# PCB-JACKGPI.net
KiCad netlist of a schematic drawn in EAGLE
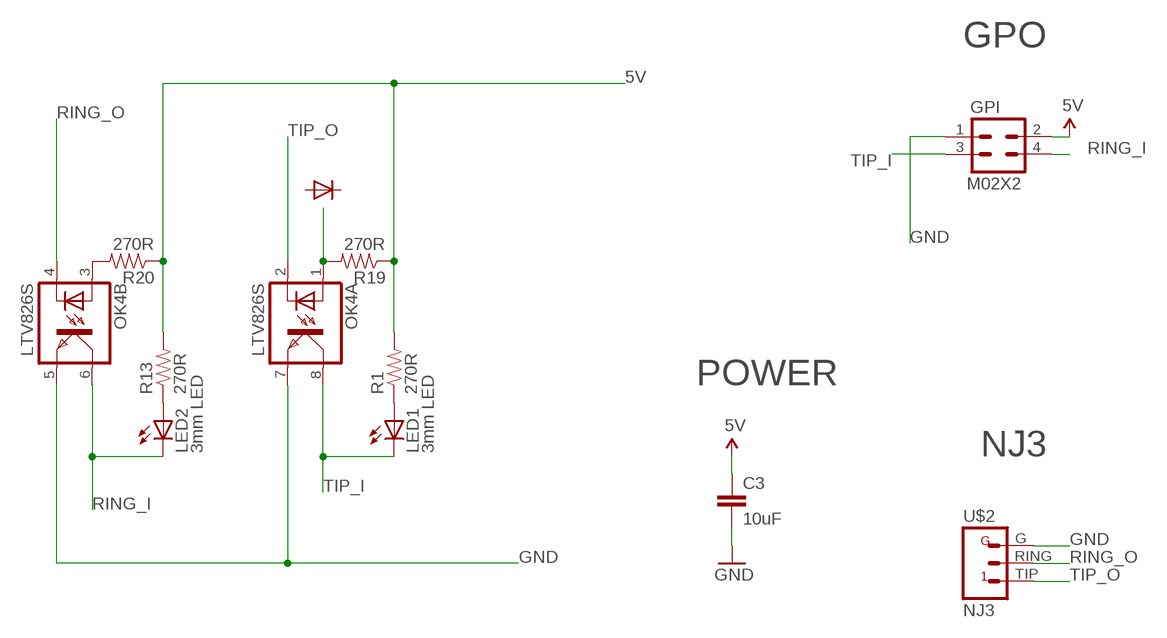
[diagram p0: schematic, sheet 1]

(export (version "E")
  (design (tool "Eeschema 10.0.6"))
  (components
    (comp (ref "C3")
      (value "10uF")
      (footprint "eagle-import:0805")
      (libsource (lib "eagle-import") (part "CAP0805"))
    )
    (comp (ref "GPI")
      (value "M02X2")
      (footprint "eagle-import:2X2")
      (libsource (lib "eagle-import") (part "M02X2"))
    )
    (comp (ref "LED1")
      (value "3mm LED")
      (footprint "eagle-import:LED3MM")
      (libsource (lib "eagle-import") (part "LED3MM"))
    )
    (comp (ref "LED2")
      (value "3mm LED")
      (footprint "eagle-import:LED3MM")
      (libsource (lib "eagle-import") (part "LED3MM"))
    )
    (comp (ref "OK4")
      (value "LTV826S")
      (footprint "eagle-import:DIL8-SMD")
      (libsource (lib "eagle-import") (part "LTV826S"))
    )
    (comp (ref "R1")
      (value "270R")
      (footprint "eagle-import:0603-RES")
      (libsource (lib "eagle-import") (part "RESISTOR0603-RES"))
    )
    (comp (ref "R13")
      (value "270R")
      (footprint "eagle-import:0603-RES")
      (libsource (lib "eagle-import") (part "RESISTOR0603-RES"))
    )
    (comp (ref "R19")
      (value "270R")
      (footprint "eagle-import:0603-RES")
      (libsource (lib "eagle-import") (part "RESISTOR0603-RES"))
    )
    (comp (ref "R20")
      (value "270R")
      (footprint "eagle-import:0603-RES")
      (libsource (lib "eagle-import") (part "RESISTOR0603-RES"))
    )
    (comp (ref "U$2")
      (value "NJ3")
      (footprint "eagle-import:NJ3FP6C")
      (libsource (lib "eagle-import") (part "NJ3"))
    )
  )
  (nets
    (net (code "1") (name "/RING_I") (class "Default")
      (node (ref "GPI") (pin "4") (pinfunction "4_4") (pintype "passive"))
      (node (ref "LED2") (pin "K") (pinfunction "C_K") (pintype "passive"))
      (node (ref "OK4") (pin "6") (pinfunction "COL_6") (pintype "passive"))
    )
    (net (code "2") (name "/RING_O") (class "Default")
      (node (ref "OK4") (pin "4") (pinfunction "C_4") (pintype "passive"))
      (node (ref "U$2") (pin "RING") (pinfunction "2_RING") (pintype "passive"))
    )
    (net (code "3") (name "/TIP_I") (class "Default")
      (node (ref "GPI") (pin "3") (pinfunction "3_3") (pintype "passive"))
      (node (ref "LED1") (pin "K") (pinfunction "C_K") (pintype "passive"))
      (node (ref "OK4") (pin "8") (pinfunction "COL_8") (pintype "passive"))
    )
    (net (code "4") (name "/TIP_O") (class "Default")
      (node (ref "OK4") (pin "2") (pinfunction "C_2") (pintype "passive"))
      (node (ref "U$2") (pin "TIP") (pinfunction "1_TIP") (pintype "passive"))
    )
    (net (code "5") (name "5V") (class "Default")
      (node (ref "C3") (pin "1") (pinfunction "1_1") (pintype "passive"))
      (node (ref "GPI") (pin "2") (pinfunction "2_2") (pintype "passive"))
      (node (ref "R1") (pin "2") (pinfunction "2_2") (pintype "passive"))
      (node (ref "R13") (pin "2") (pinfunction "2_2") (pintype "passive"))
      (node (ref "R19") (pin "1") (pinfunction "1_1") (pintype "passive"))
      (node (ref "R20") (pin "1") (pinfunction "1_1") (pintype "passive"))
    )
    (net (code "6") (name "GND") (class "Default")
      (node (ref "C3") (pin "2") (pinfunction "2_2") (pintype "passive"))
      (node (ref "GPI") (pin "1") (pinfunction "1_1") (pintype "passive"))
      (node (ref "OK4") (pin "5") (pinfunction "EMIT_5") (pintype "passive"))
      (node (ref "OK4") (pin "7") (pinfunction "EMIT_7") (pintype "passive"))
      (node (ref "U$2") (pin "G") (pinfunction "G_G") (pintype "power_in"))
    )
    (net (code "7") (name "Net-(LED1-PadA)") (class "Default")
      (node (ref "LED1") (pin "A") (pinfunction "A_A") (pintype "passive"))
      (node (ref "R1") (pin "1") (pinfunction "1_1") (pintype "passive"))
    )
    (net (code "8") (name "Net-(LED2-PadA)") (class "Default")
      (node (ref "LED2") (pin "A") (pinfunction "A_A") (pintype "passive"))
      (node (ref "R13") (pin "1") (pinfunction "1_1") (pintype "passive"))
    )
    (net (code "9") (name "Net-(OK4A-A)") (class "Default")
      (node (ref "OK4") (pin "1") (pinfunction "A_1") (pintype "passive"))
      (node (ref "R19") (pin "2") (pinfunction "2_2") (pintype "passive"))
    )
    (net (code "10") (name "Net-(OK4B-A)") (class "Default")
      (node (ref "OK4") (pin "3") (pinfunction "A_3") (pintype "passive"))
      (node (ref "R20") (pin "2") (pinfunction "2_2") (pintype "passive"))
    )
  )
)
